# Low_Voltage_Regulator.net
KiCad netlist of a schematic drawn in EAGLE
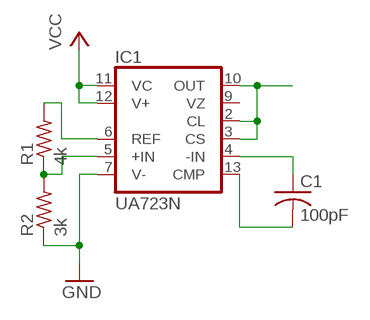
[diagram p0: schematic, sheet 1]

(export (version "E")
  (design (tool "Eeschema 10.0.6"))
  (components
    (comp (ref "C1")
      (value "100pF")
      (footprint "eagle-import:C050-025X075")
      (libsource (lib "eagle-import") (part "C-US050-025X075"))
    )
    (comp (ref "IC1")
      (value "UA723N")
      (footprint "eagle-import:DIL14")
      (libsource (lib "eagle-import") (part "723NUA"))
    )
    (comp (ref "R1")
      (value "4k")
      (footprint "eagle-import:0207_10")
      (libsource (lib "eagle-import") (part "R-US_0207/10"))
    )
    (comp (ref "R2")
      (value "3k")
      (footprint "eagle-import:0207_10")
      (libsource (lib "eagle-import") (part "R-US_0207/10"))
    )
  )
  (nets
    (net (code "1") (name "GND") (class "Default")
      (node (ref "IC1") (pin "7") (pinfunction "V-_7") (pintype "input"))
      (node (ref "R2") (pin "1") (pinfunction "1_1") (pintype "passive"))
    )
    (net (code "2") (name "Net-(IC1-+IN)") (class "Default")
      (node (ref "IC1") (pin "5") (pinfunction "+IN_5") (pintype "input"))
      (node (ref "R1") (pin "1") (pinfunction "1_1") (pintype "passive"))
      (node (ref "R2") (pin "2") (pinfunction "2_2") (pintype "passive"))
    )
    (net (code "3") (name "Net-(IC1--IN)") (class "Default")
      (node (ref "C1") (pin "1") (pinfunction "1_1") (pintype "passive"))
      (node (ref "IC1") (pin "4") (pinfunction "-IN_4") (pintype "input"))
    )
    (net (code "4") (name "Net-(IC1-CL)") (class "Default")
      (node (ref "IC1") (pin "10") (pinfunction "OUT_10") (pintype "output"))
      (node (ref "IC1") (pin "2") (pinfunction "CL_2") (pintype "input"))
      (node (ref "IC1") (pin "3") (pinfunction "CS_3") (pintype "input"))
    )
    (net (code "5") (name "Net-(IC1-CMP)") (class "Default")
      (node (ref "C1") (pin "2") (pinfunction "2_2") (pintype "passive"))
      (node (ref "IC1") (pin "13") (pinfunction "CMP_13") (pintype "passive"))
    )
    (net (code "6") (name "Net-(IC1-REF)") (class "Default")
      (node (ref "IC1") (pin "6") (pinfunction "REF_6") (pintype "output"))
      (node (ref "R1") (pin "2") (pinfunction "2_2") (pintype "passive"))
    )
    (net (code "7") (name "VCC") (class "Default")
      (node (ref "IC1") (pin "11") (pinfunction "VC_11") (pintype "input"))
      (node (ref "IC1") (pin "12") (pinfunction "V+_12") (pintype "input"))
    )
    (net (code "8") (name "unconnected-(IC1-VZ-Pad9)") (class "Default")
      (node (ref "IC1") (pin "9") (pinfunction "VZ_9") (pintype "output"))
    )
  )
)
